# ESP32-Core.net
KiCad netlist of a schematic drawn in Altium Designer
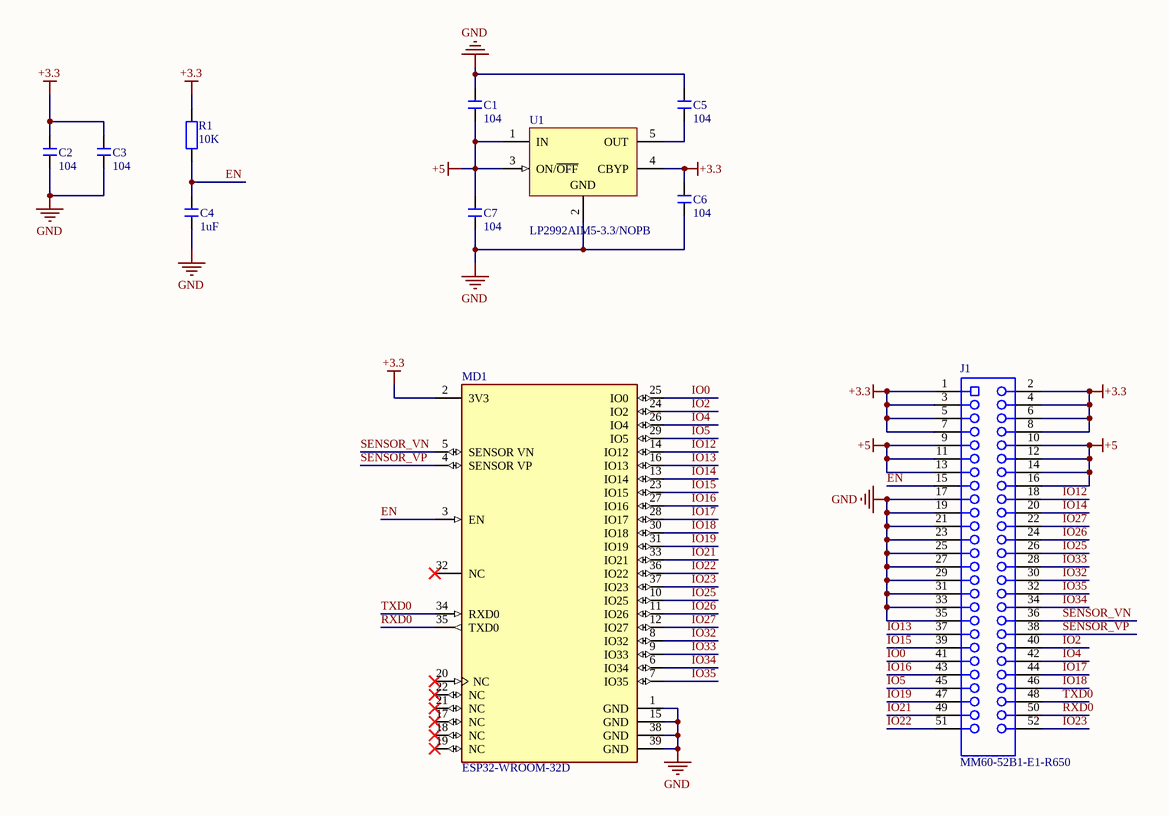
[diagram p0: ESP32-Core.SchDoc]

(export (version "E")
  (design (tool "Eeschema 10.0.6"))
  (components
    (comp (ref "C1")
      (value "104")
      (footprint "C 0603_L")
      (description "无极性贴片电容")
      (libsource (lib "电容-电阻-电感-电位器") (part "C"))
    )
    (comp (ref "C2")
      (value "104")
      (footprint "C 0603_L")
      (description "无极性贴片电容")
      (libsource (lib "电容-电阻-电感-电位器") (part "C"))
    )
    (comp (ref "C3")
      (value "104")
      (footprint "C 0603_L")
      (description "无极性贴片电容")
      (libsource (lib "电容-电阻-电感-电位器") (part "C"))
    )
    (comp (ref "C4")
      (value "1uF")
      (footprint "C 0603_L")
      (description "无极性贴片电容")
      (libsource (lib "电容-电阻-电感-电位器") (part "C"))
    )
    (comp (ref "C5")
      (value "104")
      (footprint "C 0603_L")
      (description "无极性贴片电容")
      (libsource (lib "电容-电阻-电感-电位器") (part "C"))
    )
    (comp (ref "C6")
      (value "104")
      (footprint "C 0603_L")
      (description "无极性贴片电容")
      (libsource (lib "电容-电阻-电感-电位器") (part "C"))
    )
    (comp (ref "C7")
      (value "104")
      (footprint "C 0603_L")
      (description "无极性贴片电容")
      (libsource (lib "电容-电阻-电感-电位器") (part "C"))
    )
    (comp (ref "J1")
      (value "MM60-52B1-E1-R650")
      (footprint "MINI_PCIE_GOLD_3130")
      (fields (field (name "MANUFACTURER") "JAE Electronics"))
      (libsource (lib "MINI_PCIE") (part "MINI_PCIE_GOLD"))
    )
    (comp (ref "MD1")
      (value "ESP32-WROOM-32D")
      (footprint "FP-ESP32-WROOM-32E")
      (description "WIFI MODULE 32MBITS SPI FLASH")
      (fields
        (field (name "OCTOPART") "https://octopart.com/esp32-wroom-32d-espressif+systems-91040050")
        (field (name "MANUFACTURER") "Espressif Systems")
      )
      (libsource (lib "ESP32") (part "ESP32-WROOM-32E"))
    )
    (comp (ref "R1")
      (value "10K")
      (footprint "R 0603_L")
      (description "贴片电阻")
      (libsource (lib "电容-电阻-电感-电位器") (part "R"))
    )
    (comp (ref "U1")
      (value "LP2992AIM5-3.3/NOPB")
      (footprint "MF05A_L")
      (description "Micropower 250 mA Low-Noise Ultra Low-Dropout Regulator, 5-pin SOT-23, Pb-Free")
      (fields (field (name "MANUFACTURER") "National Semiconductor"))
      (libsource (lib "Altium Content Vault") (part "PM-REG-LP2985-SOT5"))
    )
  )
  (nets
    (net (code "1") (name "+3.3") (class "Default")
      (node (ref "C2") (pin "2") (pinfunction "2_2") (pintype "passive"))
      (node (ref "C3") (pin "2") (pinfunction "2_2") (pintype "passive"))
      (node (ref "C6") (pin "2") (pinfunction "2_2") (pintype "passive"))
      (node (ref "J1") (pin "1") (pinfunction "1_1") (pintype "passive"))
      (node (ref "J1") (pin "2") (pinfunction "2_2") (pintype "passive"))
      (node (ref "J1") (pin "3") (pinfunction "3_3") (pintype "passive"))
      (node (ref "J1") (pin "4") (pinfunction "4_4") (pintype "passive"))
      (node (ref "J1") (pin "5") (pinfunction "5_5") (pintype "passive"))
      (node (ref "J1") (pin "6") (pinfunction "6_6") (pintype "passive"))
      (node (ref "J1") (pin "7") (pinfunction "7_7") (pintype "passive"))
      (node (ref "J1") (pin "8") (pinfunction "8_8") (pintype "passive"))
      (node (ref "MD1") (pin "2") (pinfunction "3V3_2") (pintype "power_in"))
      (node (ref "R1") (pin "2") (pinfunction "2_2") (pintype "passive"))
      (node (ref "U1") (pin "4") (pinfunction "CBYP_4") (pintype "passive"))
    )
    (net (code "2") (name "+5") (class "Default")
      (node (ref "C1") (pin "1") (pinfunction "1_1") (pintype "passive"))
      (node (ref "C7") (pin "2") (pinfunction "2_2") (pintype "passive"))
      (node (ref "J1") (pin "10") (pinfunction "10_10") (pintype "passive"))
      (node (ref "J1") (pin "11") (pinfunction "11_11") (pintype "passive"))
      (node (ref "J1") (pin "12") (pinfunction "12_12") (pintype "passive"))
      (node (ref "J1") (pin "13") (pinfunction "13_13") (pintype "passive"))
      (node (ref "J1") (pin "14") (pinfunction "14_14") (pintype "passive"))
      (node (ref "J1") (pin "16") (pinfunction "16_16") (pintype "passive"))
      (node (ref "J1") (pin "9") (pinfunction "9_9") (pintype "passive"))
      (node (ref "U1") (pin "1") (pinfunction "IN_1") (pintype "power_in"))
      (node (ref "U1") (pin "3") (pinfunction "ON/~{OFF}_3") (pintype "input"))
    )
    (net (code "3") (name "/EN") (class "Default")
      (node (ref "C4") (pin "2") (pinfunction "2_2") (pintype "passive"))
      (node (ref "J1") (pin "15") (pinfunction "15_15") (pintype "passive"))
      (node (ref "MD1") (pin "3") (pinfunction "EN_3") (pintype "input"))
      (node (ref "R1") (pin "1") (pinfunction "1_1") (pintype "passive"))
    )
    (net (code "4") (name "/IO0") (class "Default")
      (node (ref "J1") (pin "41") (pinfunction "41_41") (pintype "passive"))
      (node (ref "MD1") (pin "25") (pinfunction "IO0_25") (pintype "bidirectional"))
    )
    (net (code "5") (name "/IO2") (class "Default")
      (node (ref "J1") (pin "40") (pinfunction "40_40") (pintype "passive"))
      (node (ref "MD1") (pin "24") (pinfunction "IO2_24") (pintype "bidirectional"))
    )
    (net (code "6") (name "/IO4") (class "Default")
      (node (ref "J1") (pin "42") (pinfunction "42_42") (pintype "passive"))
      (node (ref "MD1") (pin "26") (pinfunction "IO4_26") (pintype "bidirectional"))
    )
    (net (code "7") (name "/IO5") (class "Default")
      (node (ref "J1") (pin "45") (pinfunction "45_45") (pintype "passive"))
      (node (ref "MD1") (pin "29") (pinfunction "IO5_29") (pintype "bidirectional"))
    )
    (net (code "8") (name "/IO12") (class "Default")
      (node (ref "J1") (pin "18") (pinfunction "18_18") (pintype "passive"))
      (node (ref "MD1") (pin "14") (pinfunction "IO12_14") (pintype "bidirectional"))
    )
    (net (code "9") (name "/IO13") (class "Default")
      (node (ref "J1") (pin "37") (pinfunction "37_37") (pintype "passive"))
      (node (ref "MD1") (pin "16") (pinfunction "IO13_16") (pintype "bidirectional"))
    )
    (net (code "10") (name "/IO14") (class "Default")
      (node (ref "J1") (pin "20") (pinfunction "20_20") (pintype "passive"))
      (node (ref "MD1") (pin "13") (pinfunction "IO14_13") (pintype "bidirectional"))
    )
    (net (code "11") (name "/IO15") (class "Default")
      (node (ref "J1") (pin "39") (pinfunction "39_39") (pintype "passive"))
      (node (ref "MD1") (pin "23") (pinfunction "IO15_23") (pintype "bidirectional"))
    )
    (net (code "12") (name "/IO16") (class "Default")
      (node (ref "J1") (pin "43") (pinfunction "43_43") (pintype "passive"))
      (node (ref "MD1") (pin "27") (pinfunction "IO16_27") (pintype "bidirectional"))
    )
    (net (code "13") (name "/IO17") (class "Default")
      (node (ref "J1") (pin "44") (pinfunction "44_44") (pintype "passive"))
      (node (ref "MD1") (pin "28") (pinfunction "IO17_28") (pintype "bidirectional"))
    )
    (net (code "14") (name "/IO18") (class "Default")
      (node (ref "J1") (pin "46") (pinfunction "46_46") (pintype "passive"))
      (node (ref "MD1") (pin "30") (pinfunction "IO18_30") (pintype "bidirectional"))
    )
    (net (code "15") (name "/IO19") (class "Default")
      (node (ref "J1") (pin "47") (pinfunction "47_47") (pintype "passive"))
      (node (ref "MD1") (pin "31") (pinfunction "IO19_31") (pintype "bidirectional"))
    )
    (net (code "16") (name "/IO21") (class "Default")
      (node (ref "J1") (pin "49") (pinfunction "49_49") (pintype "passive"))
      (node (ref "MD1") (pin "33") (pinfunction "IO21_33") (pintype "bidirectional"))
    )
    (net (code "17") (name "/IO22") (class "Default")
      (node (ref "J1") (pin "51") (pinfunction "51_51") (pintype "passive"))
      (node (ref "MD1") (pin "36") (pinfunction "IO22_36") (pintype "bidirectional"))
    )
    (net (code "18") (name "/IO23") (class "Default")
      (node (ref "J1") (pin "52") (pinfunction "52_52") (pintype "passive"))
      (node (ref "MD1") (pin "37") (pinfunction "IO23_37") (pintype "bidirectional"))
    )
    (net (code "19") (name "/IO25") (class "Default")
      (node (ref "J1") (pin "26") (pinfunction "26_26") (pintype "passive"))
      (node (ref "MD1") (pin "10") (pinfunction "IO25_10") (pintype "bidirectional"))
    )
    (net (code "20") (name "/IO26") (class "Default")
      (node (ref "J1") (pin "24") (pinfunction "24_24") (pintype "passive"))
      (node (ref "MD1") (pin "11") (pinfunction "IO26_11") (pintype "bidirectional"))
    )
    (net (code "21") (name "/IO27") (class "Default")
      (node (ref "J1") (pin "22") (pinfunction "22_22") (pintype "passive"))
      (node (ref "MD1") (pin "12") (pinfunction "IO27_12") (pintype "bidirectional"))
    )
    (net (code "22") (name "/IO32") (class "Default")
      (node (ref "J1") (pin "30") (pinfunction "30_30") (pintype "passive"))
      (node (ref "MD1") (pin "8") (pinfunction "IO32_8") (pintype "bidirectional"))
    )
    (net (code "23") (name "/IO33") (class "Default")
      (node (ref "J1") (pin "28") (pinfunction "28_28") (pintype "passive"))
      (node (ref "MD1") (pin "9") (pinfunction "IO33_9") (pintype "bidirectional"))
    )
    (net (code "24") (name "/IO34") (class "Default")
      (node (ref "J1") (pin "34") (pinfunction "34_34") (pintype "passive"))
      (node (ref "MD1") (pin "6") (pinfunction "IO34_6") (pintype "bidirectional"))
    )
    (net (code "25") (name "/IO35") (class "Default")
      (node (ref "J1") (pin "32") (pinfunction "32_32") (pintype "passive"))
      (node (ref "MD1") (pin "7") (pinfunction "IO35_7") (pintype "bidirectional"))
    )
    (net (code "26") (name "/RXD0") (class "Default")
      (node (ref "J1") (pin "50") (pinfunction "50_50") (pintype "passive"))
      (node (ref "MD1") (pin "35") (pinfunction "TXD0_35") (pintype "output"))
    )
    (net (code "27") (name "/SENSOR_VN") (class "Default")
      (node (ref "J1") (pin "36") (pinfunction "36_36") (pintype "passive"))
      (node (ref "MD1") (pin "5") (pinfunction "SENSOR_VN_5") (pintype "bidirectional"))
    )
    (net (code "28") (name "/SENSOR_VP") (class "Default")
      (node (ref "J1") (pin "38") (pinfunction "38_38") (pintype "passive"))
      (node (ref "MD1") (pin "4") (pinfunction "SENSOR_VP_4") (pintype "bidirectional"))
    )
    (net (code "29") (name "/TXD0") (class "Default")
      (node (ref "J1") (pin "48") (pinfunction "48_48") (pintype "passive"))
      (node (ref "MD1") (pin "34") (pinfunction "RXD0_34") (pintype "input"))
    )
    (net (code "30") (name "GND") (class "Default")
      (node (ref "C1") (pin "2") (pinfunction "2_2") (pintype "passive"))
      (node (ref "C2") (pin "1") (pinfunction "1_1") (pintype "passive"))
      (node (ref "C3") (pin "1") (pinfunction "1_1") (pintype "passive"))
      (node (ref "C4") (pin "1") (pinfunction "1_1") (pintype "passive"))
      (node (ref "C5") (pin "1") (pinfunction "1_1") (pintype "passive"))
      (node (ref "C6") (pin "1") (pinfunction "1_1") (pintype "passive"))
      (node (ref "C7") (pin "1") (pinfunction "1_1") (pintype "passive"))
      (node (ref "J1") (pin "17") (pinfunction "17_17") (pintype "passive"))
      (node (ref "J1") (pin "19") (pinfunction "19_19") (pintype "passive"))
      (node (ref "J1") (pin "21") (pinfunction "21_21") (pintype "passive"))
      (node (ref "J1") (pin "23") (pinfunction "23_23") (pintype "passive"))
      (node (ref "J1") (pin "25") (pinfunction "25_25") (pintype "passive"))
      (node (ref "J1") (pin "27") (pinfunction "27_27") (pintype "passive"))
      (node (ref "J1") (pin "29") (pinfunction "29_29") (pintype "passive"))
      (node (ref "J1") (pin "31") (pinfunction "31_31") (pintype "passive"))
      (node (ref "J1") (pin "33") (pinfunction "33_33") (pintype "passive"))
      (node (ref "J1") (pin "35") (pinfunction "35_35") (pintype "passive"))
      (node (ref "MD1") (pin "1") (pinfunction "GND_1") (pintype "power_in"))
      (node (ref "MD1") (pin "15") (pinfunction "GND_15") (pintype "power_in"))
      (node (ref "MD1") (pin "38") (pinfunction "GND_38") (pintype "power_in"))
      (node (ref "MD1") (pin "39") (pinfunction "GND_39") (pintype "power_in"))
      (node (ref "U1") (pin "2") (pinfunction "GND_2") (pintype "power_in"))
    )
    (net (code "31") (name "Net-(U1-OUT)") (class "Default")
      (node (ref "C5") (pin "2") (pinfunction "2_2") (pintype "passive"))
      (node (ref "U1") (pin "5") (pinfunction "OUT_5") (pintype "power_in"))
    )
    (net (code "32") (name "unconnected-(MD1-NC-Pad17)") (class "Default")
      (node (ref "MD1") (pin "17") (pinfunction "NC_17") (pintype "bidirectional+no_connect"))
    )
    (net (code "33") (name "unconnected-(MD1-NC-Pad18)") (class "Default")
      (node (ref "MD1") (pin "18") (pinfunction "NC_18") (pintype "bidirectional+no_connect"))
    )
    (net (code "34") (name "unconnected-(MD1-NC-Pad19)") (class "Default")
      (node (ref "MD1") (pin "19") (pinfunction "NC_19") (pintype "bidirectional+no_connect"))
    )
    (net (code "35") (name "unconnected-(MD1-NC-Pad20)") (class "Default")
      (node (ref "MD1") (pin "20") (pinfunction "NC_20") (pintype "input+no_connect"))
    )
    (net (code "36") (name "unconnected-(MD1-NC-Pad21)") (class "Default")
      (node (ref "MD1") (pin "21") (pinfunction "NC_21") (pintype "bidirectional+no_connect"))
    )
    (net (code "37") (name "unconnected-(MD1-NC-Pad22)") (class "Default")
      (node (ref "MD1") (pin "22") (pinfunction "NC_22") (pintype "bidirectional+no_connect"))
    )
    (net (code "38") (name "unconnected-(MD1-NC-Pad32)") (class "Default")
      (node (ref "MD1") (pin "32") (pinfunction "NC_32") (pintype "passive+no_connect"))
    )
  )
)
